# LedDriver.net
KiCad netlist of a schematic drawn in Altium Designer
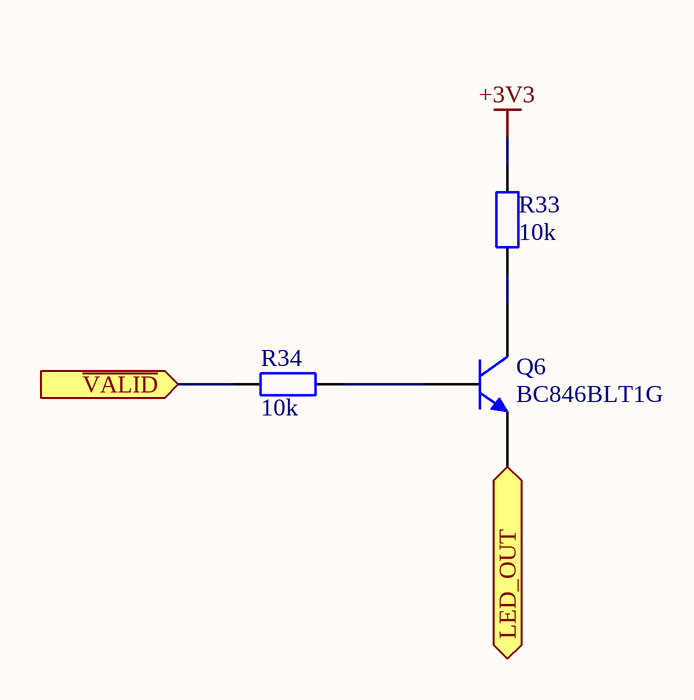
[diagram p0: LedDriver.SchDoc]

(export (version "E")
  (design (tool "Eeschema 10.0.6"))
  (components
    (comp (ref "Q6")
      (value "BC846BLT1G")
      (footprint "SOT-23-TT3_N")
      (description "NPN Bipolar Transistor")
      (fields (field (name "PUBLISHER") "Altium Limited"))
      (libsource (lib "Miscellaneous Devices") (part "NPN"))
    )
    (comp (ref "R33")
      (value "10k")
      (footprint "R2012")
      (description "Resistor")
      (fields (field (name "PUBLISHER") "Altium Limited"))
      (libsource (lib "Miscellaneous Devices") (part "Res2"))
    )
    (comp (ref "R34")
      (value "10k")
      (footprint "R2012")
      (description "Resistor")
      (fields (field (name "PUBLISHER") "Altium Limited"))
      (libsource (lib "") (part "Res2_1"))
    )
  )
  (nets
    (net (code "1") (name "+3V3") (class "Default")
      (node (ref "R33") (pin "2") (pinfunction "2_2") (pintype "passive"))
    )
    (net (code "2") (name "/LED_OUT") (class "Default")
      (node (ref "Q6") (pin "2") (pinfunction "E_2") (pintype "passive"))
    )
    (net (code "3") (name "/VALID") (class "Default")
      (node (ref "R34") (pin "2") (pinfunction "2_2") (pintype "passive"))
    )
    (net (code "4") (name "Net-(Q6-B)") (class "Default")
      (node (ref "Q6") (pin "1") (pinfunction "B_1") (pintype "passive"))
      (node (ref "R34") (pin "1") (pinfunction "1_1") (pintype "passive"))
    )
    (net (code "5") (name "Net-(Q6-C)") (class "Default")
      (node (ref "Q6") (pin "3") (pinfunction "C_3") (pintype "passive"))
      (node (ref "R33") (pin "1") (pinfunction "1_1") (pintype "passive"))
    )
  )
)
